# STorM32_NT_Display_v13.net
KiCad netlist of a schematic drawn in EAGLE
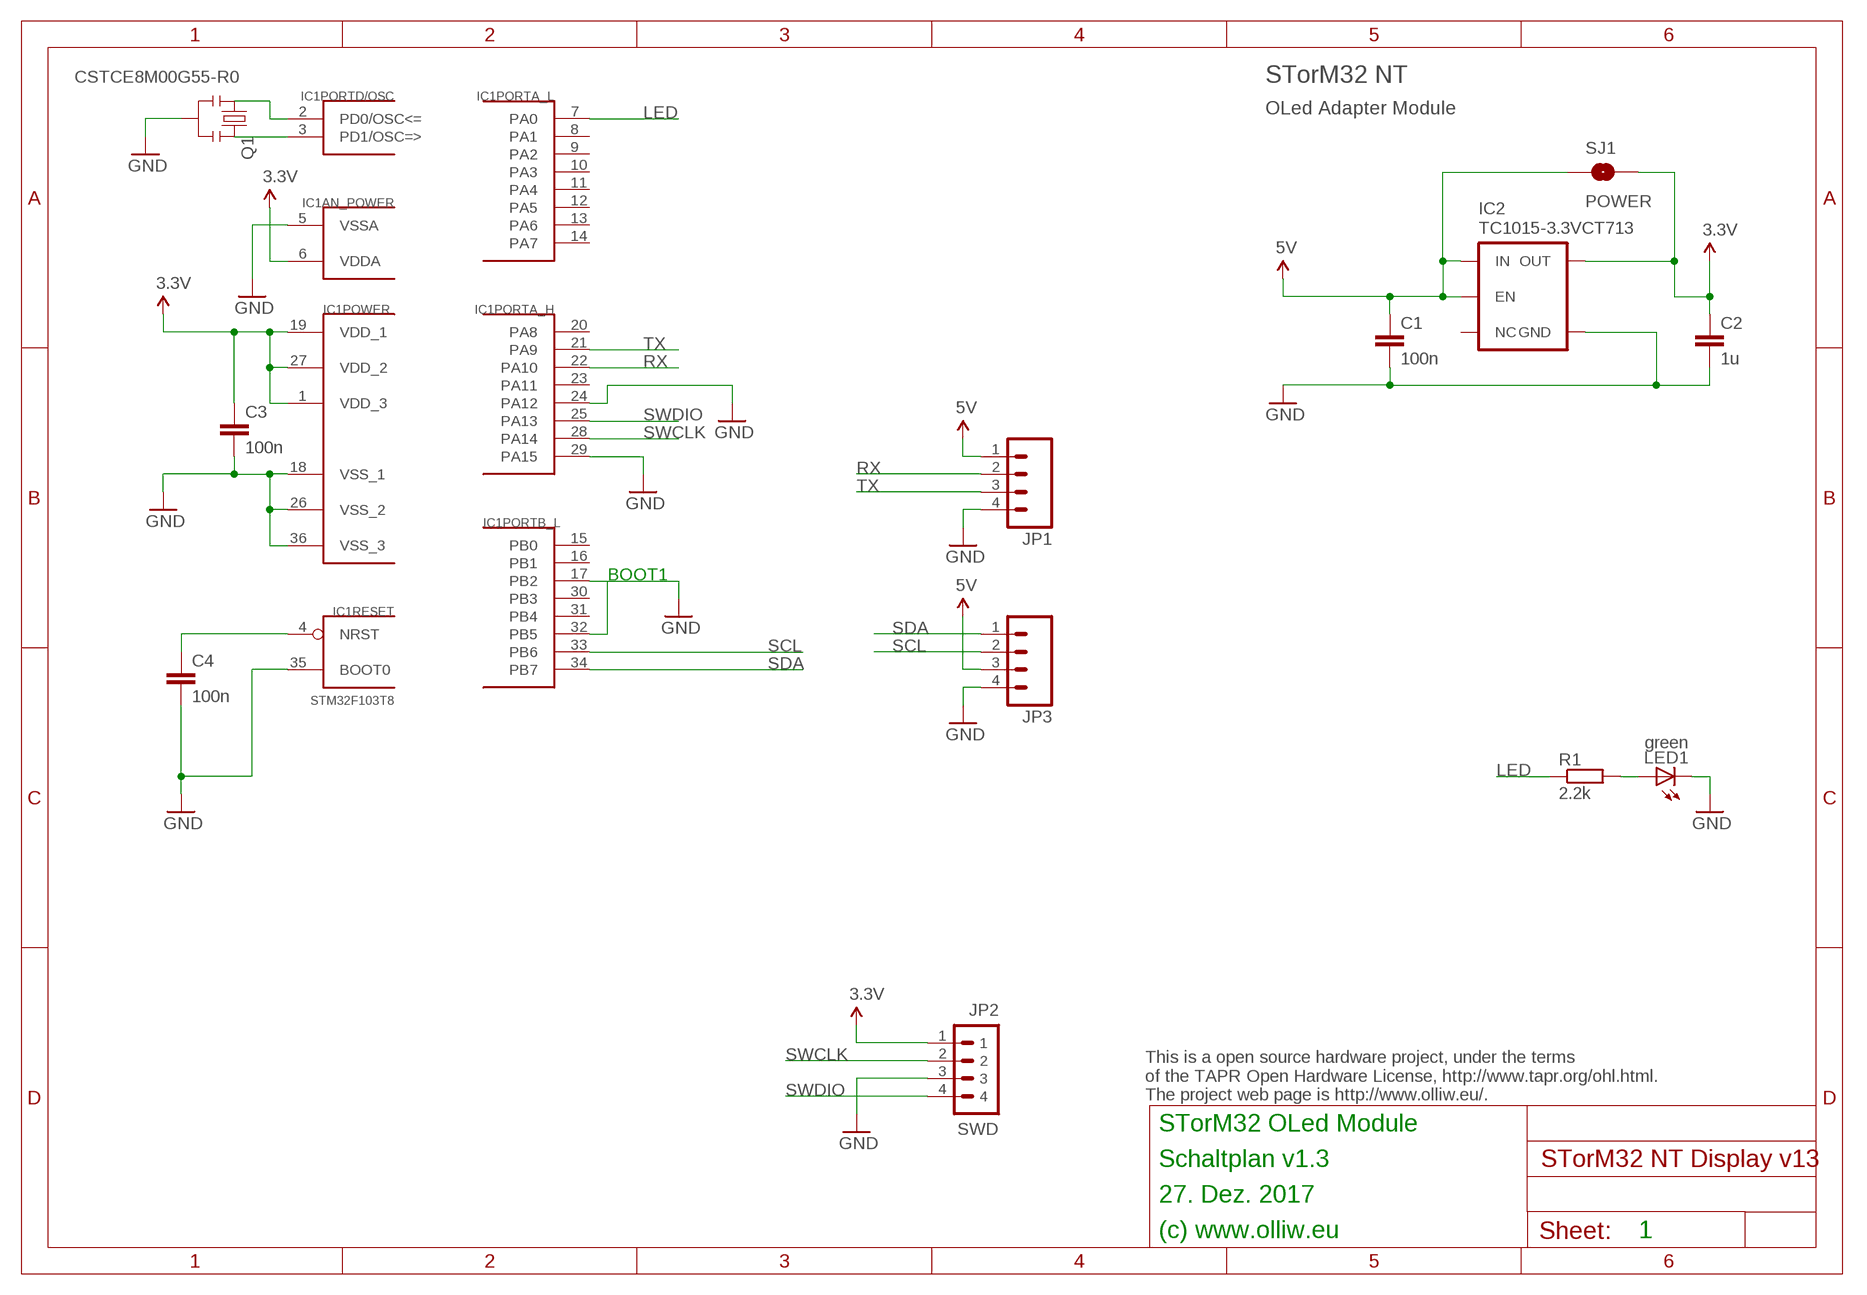
[diagram p0: schematic, sheet 1]

(export (version "E")
  (design (tool "Eeschema 10.0.6"))
  (components
    (comp (ref "C1")
      (value "100n")
      (footprint "eagle-import:C0603")
      (libsource (lib "eagle-import") (part "C-EUC0603"))
    )
    (comp (ref "C2")
      (value "1u")
      (footprint "eagle-import:C0603")
      (libsource (lib "eagle-import") (part "C-EUC0603"))
    )
    (comp (ref "C3")
      (value "100n")
      (footprint "eagle-import:C0603")
      (libsource (lib "eagle-import") (part "C-EUC0603"))
    )
    (comp (ref "C4")
      (value "100n")
      (footprint "eagle-import:C0603")
      (libsource (lib "eagle-import") (part "C-EUC0603"))
    )
    (comp (ref "IC1")
      (value "STM32F103T8")
      (footprint "eagle-import:VFQFPN36")
      (libsource (lib "eagle-import") (part "STM32F10XTXU6"))
    )
    (comp (ref "IC2")
      (value "TC1015-3.3VCT713")
      (footprint "eagle-import:SOT23-5")
      (libsource (lib "eagle-import") (part "V_REG_TPS76433SOT23-5"))
    )
    (comp (ref "JP1")
      (value "M04PTH")
      (footprint "eagle-import:1X04")
      (libsource (lib "eagle-import") (part "M04PTH"))
    )
    (comp (ref "JP2")
      (value "SWD")
      (footprint "eagle-import:4X1_1P27_OCT_BILEX")
      (libsource (lib "eagle-import") (part "P4X1_1P27-OCT_BILEX"))
    )
    (comp (ref "JP3")
      (value "M04PTH")
      (footprint "eagle-import:1X04")
      (libsource (lib "eagle-import") (part "M04PTH"))
    )
    (comp (ref "LED1")
      (value "green")
      (footprint "eagle-import:CHIPLED_0603")
      (libsource (lib "eagle-import") (part "LEDCHIPLED_0603"))
    )
    (comp (ref "Q1")
      (value "CSTCE8M00G55-R0")
      (footprint "eagle-import:RESONATOR-SMD")
      (libsource (lib "eagle-import") (part "RESONATORSMD"))
    )
    (comp (ref "R1")
      (value "2.2k")
      (footprint "eagle-import:R0603")
      (libsource (lib "eagle-import") (part "R-EU_R0603"))
    )
    (comp (ref "SJ1")
      (value "POWER")
      (footprint "eagle-import:SJ_2S-NO")
      (libsource (lib "eagle-import") (part "SOLDERJUMPERNO"))
    )
  )
  (nets
    (net (code "1") (name "/LED") (class "Default")
      (node (ref "IC1") (pin "7") (pinfunction "PA0_7") (pintype "bidirectional"))
      (node (ref "R1") (pin "1") (pinfunction "1_1") (pintype "passive"))
    )
    (net (code "2") (name "/RX") (class "Default")
      (node (ref "IC1") (pin "22") (pinfunction "PA10_22") (pintype "bidirectional"))
      (node (ref "JP1") (pin "2") (pinfunction "2_2") (pintype "passive"))
    )
    (net (code "3") (name "/SCL") (class "Default")
      (node (ref "IC1") (pin "33") (pinfunction "PB6_33") (pintype "bidirectional"))
      (node (ref "JP3") (pin "2") (pinfunction "2_2") (pintype "passive"))
    )
    (net (code "4") (name "/SDA") (class "Default")
      (node (ref "IC1") (pin "34") (pinfunction "PB7_34") (pintype "bidirectional"))
      (node (ref "JP3") (pin "1") (pinfunction "1_1") (pintype "passive"))
    )
    (net (code "5") (name "/SWCLK") (class "Default")
      (node (ref "IC1") (pin "28") (pinfunction "PA14_28") (pintype "bidirectional"))
      (node (ref "JP2") (pin "2") (pinfunction "2_2") (pintype "passive"))
    )
    (net (code "6") (name "/SWDIO") (class "Default")
      (node (ref "IC1") (pin "25") (pinfunction "PA13_25") (pintype "bidirectional"))
      (node (ref "JP2") (pin "4") (pinfunction "4_4") (pintype "passive"))
    )
    (net (code "7") (name "/TX") (class "Default")
      (node (ref "IC1") (pin "21") (pinfunction "PA9_21") (pintype "bidirectional"))
      (node (ref "JP1") (pin "3") (pinfunction "3_3") (pintype "passive"))
    )
    (net (code "8") (name "3.3V") (class "Default")
      (node (ref "C2") (pin "1") (pinfunction "1_1") (pintype "passive"))
      (node (ref "C3") (pin "1") (pinfunction "1_1") (pintype "passive"))
      (node (ref "IC1") (pin "1") (pinfunction "VDD_3_1") (pintype "power_in"))
      (node (ref "IC1") (pin "19") (pinfunction "VDD_1_19") (pintype "power_in"))
      (node (ref "IC1") (pin "27") (pinfunction "VDD_2_27") (pintype "power_in"))
      (node (ref "IC1") (pin "6") (pinfunction "VDDA_6") (pintype "power_in"))
      (node (ref "IC2") (pin "5") (pinfunction "OUT_5") (pintype "passive"))
      (node (ref "JP2") (pin "1") (pinfunction "1_1") (pintype "passive"))
      (node (ref "SJ1") (pin "2") (pinfunction "2_2") (pintype "passive"))
    )
    (net (code "9") (name "5V") (class "Default")
      (node (ref "C1") (pin "1") (pinfunction "1_1") (pintype "passive"))
      (node (ref "IC2") (pin "1") (pinfunction "IN_1") (pintype "input"))
      (node (ref "IC2") (pin "3") (pinfunction "EN_3") (pintype "input"))
      (node (ref "JP1") (pin "1") (pinfunction "1_1") (pintype "passive"))
      (node (ref "JP3") (pin "3") (pinfunction "3_3") (pintype "passive"))
      (node (ref "SJ1") (pin "1") (pinfunction "1_1") (pintype "passive"))
    )
    (net (code "10") (name "GND") (class "Default")
      (node (ref "C1") (pin "2") (pinfunction "2_2") (pintype "passive"))
      (node (ref "C2") (pin "2") (pinfunction "2_2") (pintype "passive"))
      (node (ref "C3") (pin "2") (pinfunction "2_2") (pintype "passive"))
      (node (ref "C4") (pin "2") (pinfunction "2_2") (pintype "passive"))
      (node (ref "IC1") (pin "17") (pinfunction "PB2_17") (pintype "bidirectional"))
      (node (ref "IC1") (pin "18") (pinfunction "VSS_1_18") (pintype "power_in"))
      (node (ref "IC1") (pin "24") (pinfunction "PA12_24") (pintype "bidirectional"))
      (node (ref "IC1") (pin "26") (pinfunction "VSS_2_26") (pintype "power_in"))
      (node (ref "IC1") (pin "29") (pinfunction "PA15_29") (pintype "bidirectional"))
      (node (ref "IC1") (pin "32") (pinfunction "PB5_32") (pintype "bidirectional"))
      (node (ref "IC1") (pin "35") (pinfunction "BOOT0_35") (pintype "input"))
      (node (ref "IC1") (pin "36") (pinfunction "VSS_3_36") (pintype "power_in"))
      (node (ref "IC1") (pin "5") (pinfunction "VSSA_5") (pintype "power_in"))
      (node (ref "IC2") (pin "2") (pinfunction "GND_2") (pintype "input"))
      (node (ref "JP1") (pin "4") (pinfunction "4_4") (pintype "passive"))
      (node (ref "JP2") (pin "3") (pinfunction "3_3") (pintype "passive"))
      (node (ref "JP3") (pin "4") (pinfunction "4_4") (pintype "passive"))
      (node (ref "LED1") (pin "C") (pinfunction "C_C") (pintype "passive"))
      (node (ref "Q1") (pin "2") (pinfunction "2_2") (pintype "passive"))
    )
    (net (code "11") (name "Net-(IC1E-PD0{slash}OSC<=)") (class "Default")
      (node (ref "IC1") (pin "2") (pinfunction "PD0/OSC<=_2") (pintype "bidirectional"))
      (node (ref "Q1") (pin "1") (pinfunction "1_1") (pintype "passive"))
    )
    (net (code "12") (name "Net-(IC1E-PD1{slash}OSC=>)") (class "Default")
      (node (ref "IC1") (pin "3") (pinfunction "PD1/OSC=>_3") (pintype "bidirectional"))
      (node (ref "Q1") (pin "3") (pinfunction "3_3") (pintype "passive"))
    )
    (net (code "13") (name "Net-(IC1G-NRST)") (class "Default")
      (node (ref "C4") (pin "1") (pinfunction "1_1") (pintype "passive"))
      (node (ref "IC1") (pin "4") (pinfunction "NRST_4") (pintype "input"))
    )
    (net (code "14") (name "Net-(LED1-PadA)") (class "Default")
      (node (ref "LED1") (pin "A") (pinfunction "A_A") (pintype "passive"))
      (node (ref "R1") (pin "2") (pinfunction "2_2") (pintype "passive"))
    )
    (net (code "15") (name "unconnected-(IC1B-PA8-Pad20)") (class "Default")
      (node (ref "IC1") (pin "20") (pinfunction "PA8_20") (pintype "bidirectional"))
    )
    (net (code "16") (name "unconnected-(IC1B-PA11-Pad23)") (class "Default")
      (node (ref "IC1") (pin "23") (pinfunction "PA11_23") (pintype "bidirectional"))
    )
    (net (code "17") (name "unconnected-(IC1C-PA1-Pad8)") (class "Default")
      (node (ref "IC1") (pin "8") (pinfunction "PA1_8") (pintype "bidirectional"))
    )
    (net (code "18") (name "unconnected-(IC1C-PA2-Pad9)") (class "Default")
      (node (ref "IC1") (pin "9") (pinfunction "PA2_9") (pintype "bidirectional"))
    )
    (net (code "19") (name "unconnected-(IC1C-PA3-Pad10)") (class "Default")
      (node (ref "IC1") (pin "10") (pinfunction "PA3_10") (pintype "bidirectional"))
    )
    (net (code "20") (name "unconnected-(IC1C-PA4-Pad11)") (class "Default")
      (node (ref "IC1") (pin "11") (pinfunction "PA4_11") (pintype "bidirectional"))
    )
    (net (code "21") (name "unconnected-(IC1C-PA5-Pad12)") (class "Default")
      (node (ref "IC1") (pin "12") (pinfunction "PA5_12") (pintype "bidirectional"))
    )
    (net (code "22") (name "unconnected-(IC1C-PA6-Pad13)") (class "Default")
      (node (ref "IC1") (pin "13") (pinfunction "PA6_13") (pintype "bidirectional"))
    )
    (net (code "23") (name "unconnected-(IC1C-PA7-Pad14)") (class "Default")
      (node (ref "IC1") (pin "14") (pinfunction "PA7_14") (pintype "bidirectional"))
    )
    (net (code "24") (name "unconnected-(IC1D-PB0-Pad15)") (class "Default")
      (node (ref "IC1") (pin "15") (pinfunction "PB0_15") (pintype "bidirectional"))
    )
    (net (code "25") (name "unconnected-(IC1D-PB1-Pad16)") (class "Default")
      (node (ref "IC1") (pin "16") (pinfunction "PB1_16") (pintype "bidirectional"))
    )
    (net (code "26") (name "unconnected-(IC1D-PB3-Pad30)") (class "Default")
      (node (ref "IC1") (pin "30") (pinfunction "PB3_30") (pintype "bidirectional"))
    )
    (net (code "27") (name "unconnected-(IC1D-PB4-Pad31)") (class "Default")
      (node (ref "IC1") (pin "31") (pinfunction "PB4_31") (pintype "bidirectional"))
    )
    (net (code "28") (name "unconnected-(IC2-NC-Pad4)") (class "Default")
      (node (ref "IC2") (pin "4") (pinfunction "NC_4") (pintype "input"))
    )
  )
)
